# 24Vto48V.net
KiCad netlist of a schematic drawn in Altium Designer
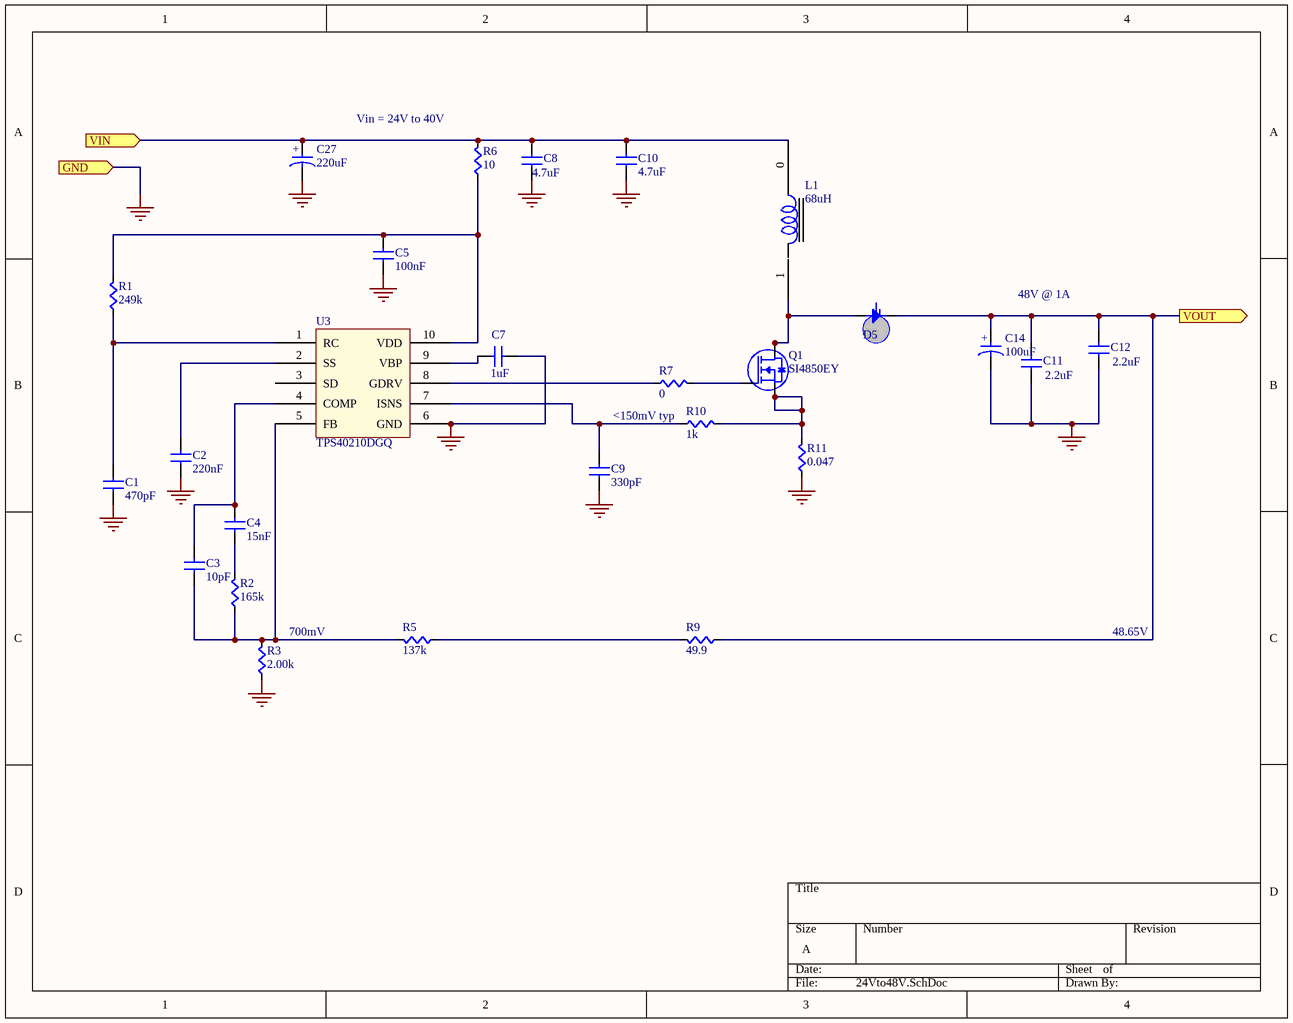
[diagram p0: 24Vto48V.SchDoc]

(export (version "E")
  (design (tool "Eeschema 10.0.6"))
  (components
    (comp (ref "C1")
      (value "470pF")
      (footprint "CAPC0603")
      (fields (field (name "Comment") "Cap"))
      (libsource (lib "Passives") (part "Cap"))
    )
    (comp (ref "C2")
      (value "220nF")
      (footprint "CAPC0603")
      (fields (field (name "Comment") "Cap"))
      (libsource (lib "Passives") (part "Cap"))
    )
    (comp (ref "C3")
      (value "10pF")
      (footprint "CAPC0603")
      (fields (field (name "Comment") "Cap"))
      (libsource (lib "Passives") (part "Cap"))
    )
    (comp (ref "C4")
      (value "15nF")
      (footprint "CAPC0603")
      (fields (field (name "Comment") "Cap"))
      (libsource (lib "Passives") (part "Cap"))
    )
    (comp (ref "C5")
      (value "100nF")
      (footprint "CAPC0603")
      (fields (field (name "Comment") "Cap"))
      (libsource (lib "Passives") (part "Cap"))
    )
    (comp (ref "C7")
      (value "1uF")
      (footprint "CAPC0603")
      (fields (field (name "Comment") "Cap"))
      (libsource (lib "Passives") (part "Cap"))
    )
    (comp (ref "C8")
      (value "4.7uF")
      (footprint "CAP1210")
      (description "CAP CER 10UF 50V 20% X5R 1210")
      (fields (field (name "Comment") "CAP1210"))
      (libsource (lib "Passives") (part "CAP1210"))
    )
    (comp (ref "C9")
      (value "330pF")
      (footprint "CAPC0603")
      (fields (field (name "Comment") "Cap"))
      (libsource (lib "Passives") (part "Cap"))
    )
    (comp (ref "C10")
      (value "4.7uF")
      (footprint "CAP1210")
      (description "CAP CER 10UF 50V 20% X5R 1210")
      (fields (field (name "Comment") "CAP1210"))
      (libsource (lib "Passives") (part "CAP1210"))
    )
    (comp (ref "C11")
      (value "2.2uF")
      (footprint "CAP1210")
      (description "CAP CER 10UF 50V 20% X5R 1210")
      (fields (field (name "Comment") "CAP1210"))
      (libsource (lib "Passives") (part "CAP1210"))
    )
    (comp (ref "C12")
      (value "2.2uF")
      (footprint "CAP1210")
      (description "CAP CER 10UF 50V 20% X5R 1210")
      (fields (field (name "Comment") "CAP1210"))
      (libsource (lib "Passives") (part "CAP1210"))
    )
    (comp (ref "C14")
      (value "100uF")
      (footprint "565-1720-ND")
      (description "100 uF CAP ALUM 20% 63V RADIAL")
      (fields (field (name "Comment") "Cap Tant"))
      (libsource (lib "Passives") (part "CapPol"))
    )
    (comp (ref "C27")
      (value "220uF")
      (footprint "ESY227M050AH2AA")
      (description "CAP ALUM 220UF")
      (fields (field (name "Comment") "Cap Tant"))
      (libsource (lib "Passives") (part "CapPol"))
    )
    (comp (ref "D5")
      (value "Diode")
      (footprint "MBRS360SMB")
      (description "Standard Diode Template")
      (libsource (lib "Semiconductors") (part "Diode"))
    )
    (comp (ref "L1")
      (value "68uH")
      (footprint "732-1247-1-ND")
      (description "INDUCTOR 3.90UH 10.0A SMD")
      (fields (field (name "Comment") "37392C"))
      (libsource (lib "Passives") (part "37392C"))
    )
    (comp (ref "Q1")
      (value "SI4850EY")
      (footprint "SOIC-8-NO-EP")
      (description "MOSFET N-CH 60V 6A 8-SOIC")
      (libsource (lib "Semiconductors") (part "SI4850EY"))
    )
    (comp (ref "R1")
      (value "249k")
      (footprint "RES0603")
      (fields (field (name "Comment") "Res"))
      (libsource (lib "Passives") (part "Res"))
    )
    (comp (ref "R2")
      (value "165k")
      (footprint "RES0603")
      (fields (field (name "Comment") "Res"))
      (libsource (lib "Passives") (part "Res"))
    )
    (comp (ref "R3")
      (value "2.00k")
      (footprint "RES0603")
      (fields (field (name "Comment") "Res"))
      (libsource (lib "Passives") (part "Res"))
    )
    (comp (ref "R5")
      (value "137k")
      (footprint "RES0603")
      (fields (field (name "Comment") "Res"))
      (libsource (lib "Passives") (part "Res"))
    )
    (comp (ref "R6")
      (value "10")
      (footprint "RES0603")
      (fields (field (name "Comment") "Res"))
      (libsource (lib "Passives") (part "Res"))
    )
    (comp (ref "R7")
      (value "0")
      (footprint "RES0603")
      (fields (field (name "Comment") "Res"))
      (libsource (lib "Passives") (part "Res"))
    )
    (comp (ref "R9")
      (value "49.9")
      (footprint "RES0603")
      (fields (field (name "Comment") "Res"))
      (libsource (lib "Passives") (part "Res"))
    )
    (comp (ref "R10")
      (value "1k")
      (footprint "RES0603")
      (fields (field (name "Comment") "Res"))
      (libsource (lib "Passives") (part "Res"))
    )
    (comp (ref "R11")
      (value "0.047")
      (footprint "RES2512")
      (fields (field (name "Comment") "Res"))
      (libsource (lib "Passives") (part "Res"))
    )
    (comp (ref "U3")
      (value "TPS40210DGQ")
      (footprint "TPS40210")
      (libsource (lib "ICs") (part "TPS40210DGQ"))
    )
  )
  (nets
    (net (code "1") (name "/VIN") (class "Default")
      (node (ref "C10") (pin "1") (pinfunction "A_1") (pintype "passive"))
      (node (ref "C27") (pin "1") (pinfunction "A_1") (pintype "passive"))
      (node (ref "C8") (pin "1") (pinfunction "A_1") (pintype "passive"))
      (node (ref "L1") (pin "0") (pinfunction "0_0") (pintype "passive"))
      (node (ref "R6") (pin "1") (pinfunction "A_1") (pintype "passive"))
    )
    (net (code "2") (name "/VOUT") (class "Default")
      (node (ref "C11") (pin "1") (pinfunction "A_1") (pintype "passive"))
      (node (ref "C12") (pin "1") (pinfunction "A_1") (pintype "passive"))
      (node (ref "C14") (pin "1") (pinfunction "A_1") (pintype "passive"))
      (node (ref "D5") (pin "C") (pinfunction "C_C") (pintype "passive"))
      (node (ref "R9") (pin "2") (pinfunction "B_2") (pintype "passive"))
    )
    (net (code "3") (name "GND") (class "Default")
      (node (ref "C1") (pin "2") (pinfunction "B_2") (pintype "passive"))
      (node (ref "C10") (pin "2") (pinfunction "B_2") (pintype "passive"))
      (node (ref "C11") (pin "2") (pinfunction "B_2") (pintype "passive"))
      (node (ref "C12") (pin "2") (pinfunction "B_2") (pintype "passive"))
      (node (ref "C14") (pin "2") (pinfunction "B_2") (pintype "passive"))
      (node (ref "C2") (pin "2") (pinfunction "B_2") (pintype "passive"))
      (node (ref "C27") (pin "2") (pinfunction "B_2") (pintype "passive"))
      (node (ref "C5") (pin "2") (pinfunction "B_2") (pintype "passive"))
      (node (ref "C7") (pin "2") (pinfunction "B_2") (pintype "passive"))
      (node (ref "C8") (pin "2") (pinfunction "B_2") (pintype "passive"))
      (node (ref "C9") (pin "2") (pinfunction "B_2") (pintype "passive"))
      (node (ref "R11") (pin "2") (pinfunction "B_2") (pintype "passive"))
      (node (ref "R3") (pin "2") (pinfunction "B_2") (pintype "passive"))
      (node (ref "U3") (pin "6") (pinfunction "GND_6") (pintype "passive"))
    )
    (net (code "4") (name "Net-(C1-A)") (class "Default")
      (node (ref "C1") (pin "1") (pinfunction "A_1") (pintype "passive"))
      (node (ref "R1") (pin "2") (pinfunction "B_2") (pintype "passive"))
      (node (ref "U3") (pin "1") (pinfunction "RC_1") (pintype "passive"))
    )
    (net (code "5") (name "Net-(C2-A)") (class "Default")
      (node (ref "C2") (pin "1") (pinfunction "A_1") (pintype "passive"))
      (node (ref "U3") (pin "2") (pinfunction "SS_2") (pintype "passive"))
    )
    (net (code "6") (name "Net-(C3-A)") (class "Default")
      (node (ref "C3") (pin "1") (pinfunction "A_1") (pintype "passive"))
      (node (ref "C4") (pin "1") (pinfunction "A_1") (pintype "passive"))
      (node (ref "U3") (pin "4") (pinfunction "COMP_4") (pintype "passive"))
    )
    (net (code "7") (name "Net-(C3-B)") (class "Default")
      (node (ref "C3") (pin "2") (pinfunction "B_2") (pintype "passive"))
      (node (ref "R2") (pin "2") (pinfunction "B_2") (pintype "passive"))
      (node (ref "R3") (pin "1") (pinfunction "A_1") (pintype "passive"))
      (node (ref "R5") (pin "1") (pinfunction "A_1") (pintype "passive"))
      (node (ref "U3") (pin "5") (pinfunction "FB_5") (pintype "passive"))
    )
    (net (code "8") (name "Net-(C4-B)") (class "Default")
      (node (ref "C4") (pin "2") (pinfunction "B_2") (pintype "passive"))
      (node (ref "R2") (pin "1") (pinfunction "A_1") (pintype "passive"))
    )
    (net (code "9") (name "Net-(C5-A)") (class "Default")
      (node (ref "C5") (pin "1") (pinfunction "A_1") (pintype "passive"))
      (node (ref "R1") (pin "1") (pinfunction "A_1") (pintype "passive"))
      (node (ref "R6") (pin "2") (pinfunction "B_2") (pintype "passive"))
      (node (ref "U3") (pin "10") (pinfunction "VDD_10") (pintype "passive"))
    )
    (net (code "10") (name "Net-(C7-A)") (class "Default")
      (node (ref "C7") (pin "1") (pinfunction "A_1") (pintype "passive"))
      (node (ref "U3") (pin "9") (pinfunction "VBP_9") (pintype "passive"))
    )
    (net (code "11") (name "Net-(C9-A)") (class "Default")
      (node (ref "C9") (pin "1") (pinfunction "A_1") (pintype "passive"))
      (node (ref "R10") (pin "2") (pinfunction "B_2") (pintype "passive"))
      (node (ref "U3") (pin "7") (pinfunction "ISNS_7") (pintype "passive"))
    )
    (net (code "12") (name "Net-(D5-PadA)") (class "Default")
      (node (ref "D5") (pin "A") (pinfunction "A_A") (pintype "passive"))
      (node (ref "L1") (pin "1") (pinfunction "1_1") (pintype "passive"))
      (node (ref "Q1") (pin "5") (pinfunction "D_5") (pintype "passive"))
      (node (ref "Q1") (pin "6") (pinfunction "D_6") (pintype "passive"))
      (node (ref "Q1") (pin "7") (pinfunction "D_7") (pintype "passive"))
      (node (ref "Q1") (pin "8") (pinfunction "D_8") (pintype "passive"))
    )
    (net (code "13") (name "Net-(Q1-G)") (class "Default")
      (node (ref "Q1") (pin "4") (pinfunction "G_4") (pintype "passive"))
      (node (ref "R7") (pin "1") (pinfunction "A_1") (pintype "passive"))
    )
    (net (code "14") (name "Net-(R5-B)") (class "Default")
      (node (ref "R5") (pin "2") (pinfunction "B_2") (pintype "passive"))
      (node (ref "R9") (pin "1") (pinfunction "A_1") (pintype "passive"))
    )
    (net (code "15") (name "Net-(R7-B)") (class "Default")
      (node (ref "R7") (pin "2") (pinfunction "B_2") (pintype "passive"))
      (node (ref "U3") (pin "8") (pinfunction "GDRV_8") (pintype "passive"))
    )
    (net (code "16") (name "Net-(R10-A)") (class "Default")
      (node (ref "Q1") (pin "1") (pinfunction "S_1") (pintype "passive"))
      (node (ref "Q1") (pin "2") (pinfunction "S_2") (pintype "passive"))
      (node (ref "Q1") (pin "3") (pinfunction "S_3") (pintype "passive"))
      (node (ref "R10") (pin "1") (pinfunction "A_1") (pintype "passive"))
      (node (ref "R11") (pin "1") (pinfunction "A_1") (pintype "passive"))
    )
    (net (code "17") (name "unconnected-(U3-SD-Pad3)") (class "Default")
      (node (ref "U3") (pin "3") (pinfunction "SD_3") (pintype "passive"))
    )
  )
)
